# Sheet6.net
KiCad netlist of a schematic drawn in Altium Designer
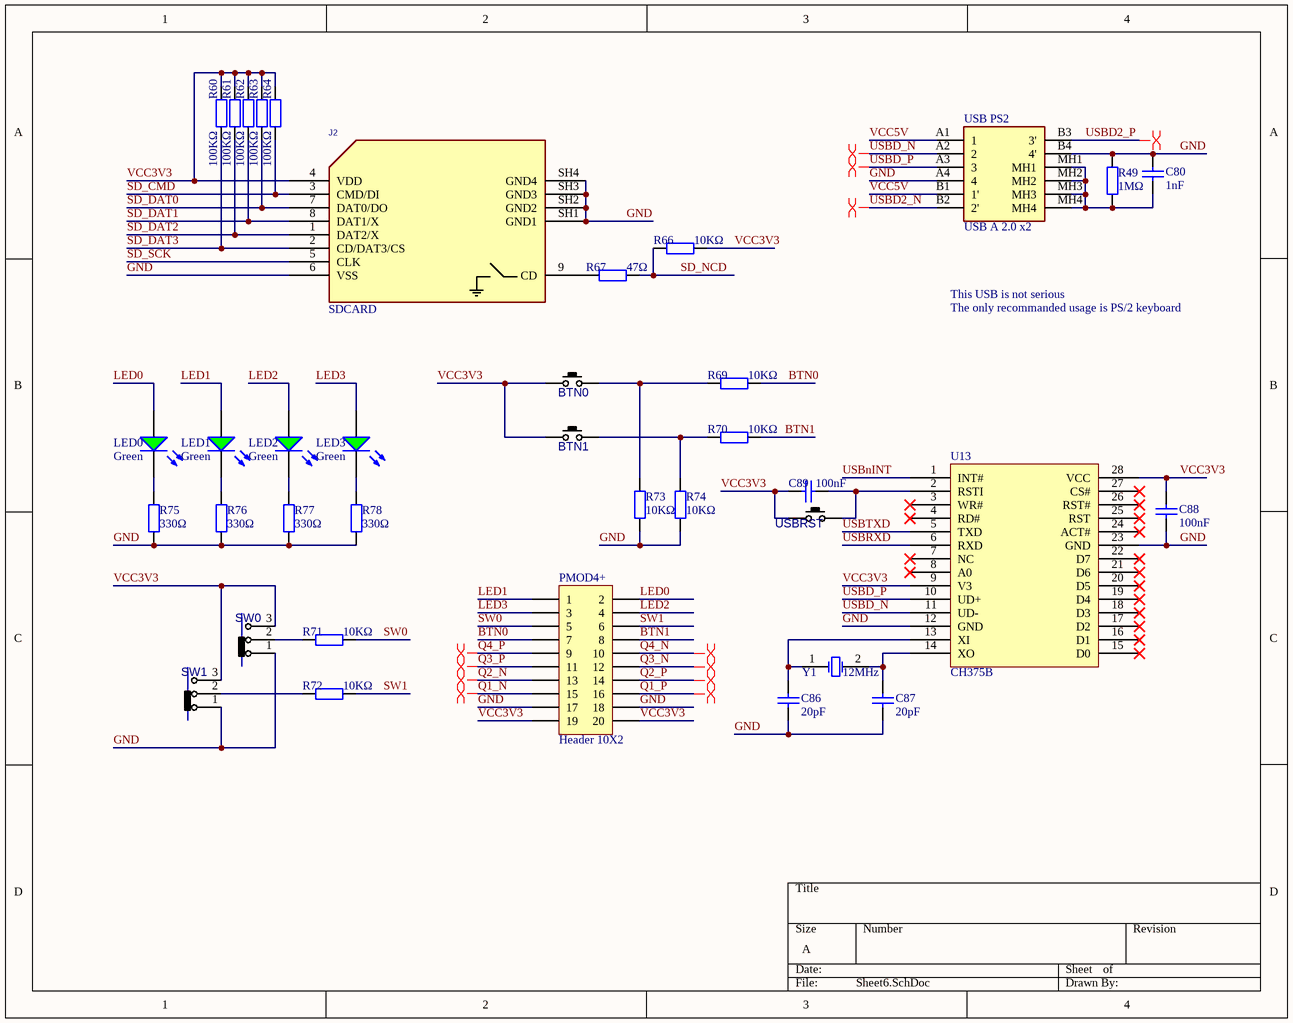
[diagram p0: Sheet6.SchDoc]

(export (version "E")
  (design (tool "Eeschema 10.0.6"))
  (components
    (comp (ref "BTN0")
      (value "PUSHBUTTON")
      (footprint "SWPBS_SPST_6X3X5")
      (description "SWITCH, PUSH BUTTON, TACTILE, SMD, SPST, 6X3.5X4.3mm")
      (fields (field (name "MANF") "Panasonic") (field (name "MANF_P#") "EVQ-PNF04M"))
      (libsource (lib "Switch Push Botton") (part "SWPBS_SPST_6X3X4"))
    )
    (comp (ref "BTN1")
      (value "PUSHBUTTON")
      (footprint "SWPBS_SPST_6X3X5")
      (description "SWITCH, PUSH BUTTON, TACTILE, SMD, SPST, 6X3.5X4.3mm")
      (fields (field (name "MANF") "Panasonic") (field (name "MANF_P#") "EVQ-PNF04M"))
      (libsource (lib "Switch Push Botton") (part "SWPBS_SPST_6X3X4"))
    )
    (comp (ref "C80")
      (value "1nF")
      (footprint "0805_C")
      (description "贴片电容")
      (libsource (lib "Cap") (part "0805 1nF (102) 10% 50V"))
    )
    (comp (ref "C86")
      (value "20pF")
      (footprint "0805_C")
      (description "贴片电容")
      (libsource (lib "Cap") (part "0805 20pF (200) 5% 50V"))
    )
    (comp (ref "C87")
      (value "20pF")
      (footprint "0805_C")
      (description "贴片电容")
      (libsource (lib "Cap") (part "0805 20pF (200) 5% 50V"))
    )
    (comp (ref "C88")
      (value "100nF")
      (footprint "1206_C")
      (description "贴片电容")
      (libsource (lib "Cap") (part "1206 100nF (104) 10% 50V"))
    )
    (comp (ref "C89")
      (value "100nF")
      (footprint "1206_C")
      (description "贴片电容")
      (libsource (lib "Cap") (part "1206 100nF (104) 10% 50V"))
    )
    (comp (ref "J2")
      (value "SDCARD")
      (footprint "SDMICRO_AT")
      (description "SD MICRO exist in Iran, Attend 112J-TDAR-R01")
      (fields (field (name "MANF") "Attend") (field (name "MANF_P#") "112J-TDAR-R01"))
      (libsource (lib "Connector Micro SD") (part "SOCKET_SDMICRO_AT"))
    )
    (comp (ref "LED0")
      (value "Green")
      (footprint "0805_LED_S1")
      (description "发光二极管")
      (libsource (lib "LED") (part "0805 翠绿"))
    )
    (comp (ref "LED1")
      (value "Green")
      (footprint "0805_LED_S1")
      (description "发光二极管")
      (libsource (lib "LED") (part "0805 翠绿"))
    )
    (comp (ref "LED2")
      (value "Green")
      (footprint "0805_LED_S1")
      (description "发光二极管")
      (libsource (lib "LED") (part "0805 翠绿"))
    )
    (comp (ref "LED3")
      (value "Green")
      (footprint "0805_LED_S1")
      (description "发光二极管")
      (libsource (lib "LED") (part "0805 翠绿"))
    )
    (comp (ref "PMOD4+")
      (value "Header 10X2")
      (footprint "HDR2X10")
      (description "Header, 10-Pin, Dual row")
      (fields (field (name "PUBLISHER") "Altium Limited"))
      (libsource (lib "Miscellaneous Connectors") (part "Header 10X2"))
    )
    (comp (ref "R49")
      (value "1MΩ")
      (footprint "0805_R")
      (description "贴片电阻")
      (libsource (lib "RES") (part "0805 1MΩ (1004) 1%"))
    )
    (comp (ref "R60")
      (value "100KΩ")
      (footprint "1206_R")
      (description "贴片电阻")
      (libsource (lib "RES") (part "1206 100KΩ (1003) 1%"))
    )
    (comp (ref "R61")
      (value "100KΩ")
      (footprint "1206_R")
      (description "贴片电阻")
      (libsource (lib "RES") (part "1206 100KΩ (1003) 1%"))
    )
    (comp (ref "R62")
      (value "100KΩ")
      (footprint "1206_R")
      (description "贴片电阻")
      (libsource (lib "RES") (part "1206 100KΩ (1003) 1%"))
    )
    (comp (ref "R63")
      (value "100KΩ")
      (footprint "1206_R")
      (description "贴片电阻")
      (libsource (lib "RES") (part "1206 100KΩ (1003) 1%"))
    )
    (comp (ref "R64")
      (value "100KΩ")
      (footprint "1206_R")
      (description "贴片电阻")
      (libsource (lib "RES") (part "1206 100KΩ (1003) 1%"))
    )
    (comp (ref "R66")
      (value "10KΩ")
      (footprint "1206_R")
      (description "贴片电阻")
      (libsource (lib "") (part "1206 10KΩ (1002) 1%_1"))
    )
    (comp (ref "R67")
      (value "47Ω")
      (footprint "0805_R")
      (description "贴片电阻")
      (libsource (lib "RES") (part "0805 47Ω (47R0) 1%"))
    )
    (comp (ref "R69")
      (value "10KΩ")
      (footprint "1206_R")
      (description "贴片电阻")
      (libsource (lib "") (part "1206 10KΩ (1002) 1%_1"))
    )
    (comp (ref "R70")
      (value "10KΩ")
      (footprint "1206_R")
      (description "贴片电阻")
      (libsource (lib "") (part "1206 10KΩ (1002) 1%_1"))
    )
    (comp (ref "R71")
      (value "10KΩ")
      (footprint "1206_R")
      (description "贴片电阻")
      (libsource (lib "") (part "1206 10KΩ (1002) 1%_1"))
    )
    (comp (ref "R72")
      (value "10KΩ")
      (footprint "1206_R")
      (description "贴片电阻")
      (libsource (lib "") (part "1206 10KΩ (1002) 1%_1"))
    )
    (comp (ref "R73")
      (value "10KΩ")
      (footprint "1206_R")
      (description "贴片电阻")
      (libsource (lib "RES") (part "1206 10KΩ (1002) 1%"))
    )
    (comp (ref "R74")
      (value "10KΩ")
      (footprint "1206_R")
      (description "贴片电阻")
      (libsource (lib "RES") (part "1206 10KΩ (1002) 1%"))
    )
    (comp (ref "R75")
      (value "330Ω")
      (footprint "0805_R")
      (description "贴片电阻")
      (libsource (lib "RES") (part "0805 330Ω (3300) 1%"))
    )
    (comp (ref "R76")
      (value "330Ω")
      (footprint "0805_R")
      (description "贴片电阻")
      (libsource (lib "RES") (part "0805 330Ω (3300) 1%"))
    )
    (comp (ref "R77")
      (value "330Ω")
      (footprint "0805_R")
      (description "贴片电阻")
      (libsource (lib "RES") (part "0805 330Ω (3300) 1%"))
    )
    (comp (ref "R78")
      (value "330Ω")
      (footprint "0805_R")
      (description "贴片电阻")
      (libsource (lib "RES") (part "0805 330Ω (3300) 1%"))
    )
    (comp (ref "SW0")
      (value "SlideSwitch")
      (footprint "SWSLIDT_SPDT_S_8X4")
      (description "SWITCH, SLIDE, SPDT, 8.6X4.3mm, THD")
      (fields (field (name "MANF") "C&K") (field (name "MANF_PART#") "OS102011MS2QN1"))
      (libsource (lib "Switch Slide") (part "SWSLIDT_SPDT_S_8X4"))
    )
    (comp (ref "SW1")
      (value "SlideSwitch")
      (footprint "SWSLIDT_SPDT_S_8X4")
      (description "SWITCH, SLIDE, SPDT, 8.6X4.3mm, THD")
      (fields (field (name "MANF") "C&K") (field (name "MANF_PART#") "OS102011MS2QN1"))
      (libsource (lib "Switch Slide") (part "SWSLIDT_SPDT_S_8X4"))
    )
    (comp (ref "U13")
      (value "CH375B")
      (footprint "SOIC-28_300mil")
      (description "USB")
      (libsource (lib "IC") (part "CH376S_[C14166]"))
    )
    (comp (ref "USB PS2")
      (value "USB A 2.0 x2")
      (footprint "SamacSys:0672983090")
      (description "Connector")
      (fields (field (name "MANUFACTURER_PART_NUMBER") "0672983090"))
      (libsource (lib "*") (part "0672983090"))
    )
    (comp (ref "USBRST")
      (value "PUSHBUTTON")
      (footprint "SWPBS_SPST_6X3X5")
      (description "SWITCH, PUSH BUTTON, TACTILE, SMD, SPST, 6X3.5X4.3mm")
      (fields (field (name "MANF") "Panasonic") (field (name "MANF_P#") "EVQ-PNF04M"))
      (libsource (lib "Switch Push Botton") (part "SWPBS_SPST_6X3X4"))
    )
    (comp (ref "Y1")
      (value "12MHz")
      (footprint "SMD-5032_2P")
      (description "贴片晶振")
      (libsource (lib "CrystalOscillator") (part "SMD-5032_2P 11.0592MHZ 20PF 20PPM"))
    )
  )
  (nets
    (net (code "1") (name "/BTN0") (class "Default")
      (node (ref "PMOD4+") (pin "7") (pinfunction "7_7") (pintype "passive"))
      (node (ref "R69") (pin "2") (pinfunction "2_2") (pintype "passive"))
    )
    (net (code "2") (name "/BTN1") (class "Default")
      (node (ref "PMOD4+") (pin "8") (pinfunction "8_8") (pintype "passive"))
      (node (ref "R70") (pin "2") (pinfunction "2_2") (pintype "passive"))
    )
    (net (code "3") (name "/GND") (class "Default")
      (node (ref "C80") (pin "1") (pinfunction "1_1") (pintype "passive"))
      (node (ref "C86") (pin "1") (pinfunction "1_1") (pintype "passive"))
      (node (ref "C87") (pin "1") (pinfunction "1_1") (pintype "passive"))
      (node (ref "C88") (pin "1") (pinfunction "1_1") (pintype "passive"))
      (node (ref "J2") (pin "6") (pinfunction "VSS_6") (pintype "passive"))
      (node (ref "J2") (pin "SH1") (pinfunction "GND1_SH1") (pintype "passive"))
      (node (ref "J2") (pin "SH2") (pinfunction "GND2_SH2") (pintype "passive"))
      (node (ref "J2") (pin "SH3") (pinfunction "GND3_SH3") (pintype "passive"))
      (node (ref "J2") (pin "SH4") (pinfunction "GND4_SH4") (pintype "passive"))
      (node (ref "PMOD4+") (pin "17") (pinfunction "17_17") (pintype "passive"))
      (node (ref "PMOD4+") (pin "18") (pinfunction "18_18") (pintype "passive"))
      (node (ref "R49") (pin "1") (pinfunction "1_1") (pintype "passive"))
      (node (ref "R73") (pin "1") (pinfunction "1_1") (pintype "passive"))
      (node (ref "R74") (pin "1") (pinfunction "1_1") (pintype "passive"))
      (node (ref "R75") (pin "1") (pinfunction "1_1") (pintype "passive"))
      (node (ref "R76") (pin "1") (pinfunction "1_1") (pintype "passive"))
      (node (ref "R77") (pin "1") (pinfunction "1_1") (pintype "passive"))
      (node (ref "R78") (pin "1") (pinfunction "1_1") (pintype "passive"))
      (node (ref "SW0") (pin "1") (pinfunction "P1_1") (pintype "passive"))
      (node (ref "SW1") (pin "1") (pinfunction "P1_1") (pintype "passive"))
      (node (ref "U13") (pin "12") (pinfunction "GND_12") (pintype "passive"))
      (node (ref "U13") (pin "23") (pinfunction "GND_23") (pintype "passive"))
      (node (ref "USB PS2") (pin "A4") (pinfunction "4_A4") (pintype "passive"))
      (node (ref "USB PS2") (pin "B4") (pinfunction "4'_B4") (pintype "passive"))
    )
    (net (code "4") (name "/LED0") (class "Default")
      (node (ref "LED0") (pin "A") (pinfunction "A_A") (pintype "passive"))
      (node (ref "PMOD4+") (pin "2") (pinfunction "2_2") (pintype "passive"))
    )
    (net (code "5") (name "/LED1") (class "Default")
      (node (ref "LED1") (pin "A") (pinfunction "A_A") (pintype "passive"))
      (node (ref "PMOD4+") (pin "1") (pinfunction "1_1") (pintype "passive"))
    )
    (net (code "6") (name "/LED2") (class "Default")
      (node (ref "LED2") (pin "A") (pinfunction "A_A") (pintype "passive"))
      (node (ref "PMOD4+") (pin "4") (pinfunction "4_4") (pintype "passive"))
    )
    (net (code "7") (name "/LED3") (class "Default")
      (node (ref "LED3") (pin "A") (pinfunction "A_A") (pintype "passive"))
      (node (ref "PMOD4+") (pin "3") (pinfunction "3_3") (pintype "passive"))
    )
    (net (code "8") (name "/Q1_N") (class "Default")
      (node (ref "PMOD4+") (pin "15") (pinfunction "15_15") (pintype "passive"))
    )
    (net (code "9") (name "/Q1_P") (class "Default")
      (node (ref "PMOD4+") (pin "16") (pinfunction "16_16") (pintype "passive"))
    )
    (net (code "10") (name "/Q2_N") (class "Default")
      (node (ref "PMOD4+") (pin "13") (pinfunction "13_13") (pintype "passive"))
    )
    (net (code "11") (name "/Q2_P") (class "Default")
      (node (ref "PMOD4+") (pin "14") (pinfunction "14_14") (pintype "passive"))
    )
    (net (code "12") (name "/Q3_N") (class "Default")
      (node (ref "PMOD4+") (pin "12") (pinfunction "12_12") (pintype "passive"))
    )
    (net (code "13") (name "/Q3_P") (class "Default")
      (node (ref "PMOD4+") (pin "11") (pinfunction "11_11") (pintype "passive"))
    )
    (net (code "14") (name "/Q4_N") (class "Default")
      (node (ref "PMOD4+") (pin "10") (pinfunction "10_10") (pintype "passive"))
    )
    (net (code "15") (name "/Q4_P") (class "Default")
      (node (ref "PMOD4+") (pin "9") (pinfunction "9_9") (pintype "passive"))
    )
    (net (code "16") (name "/SD_CMD") (class "Default")
      (node (ref "J2") (pin "3") (pinfunction "CMD/DI_3") (pintype "passive"))
      (node (ref "R64") (pin "1") (pinfunction "1_1") (pintype "passive"))
    )
    (net (code "17") (name "/SD_DAT0") (class "Default")
      (node (ref "J2") (pin "7") (pinfunction "DAT0/DO_7") (pintype "passive"))
      (node (ref "R63") (pin "1") (pinfunction "1_1") (pintype "passive"))
    )
    (net (code "18") (name "/SD_DAT1") (class "Default")
      (node (ref "J2") (pin "8") (pinfunction "DAT1/X_8") (pintype "passive"))
      (node (ref "R62") (pin "1") (pinfunction "1_1") (pintype "passive"))
    )
    (net (code "19") (name "/SD_DAT2") (class "Default")
      (node (ref "J2") (pin "1") (pinfunction "DAT2/X_1") (pintype "passive"))
      (node (ref "R61") (pin "1") (pinfunction "1_1") (pintype "passive"))
    )
    (net (code "20") (name "/SD_DAT3") (class "Default")
      (node (ref "J2") (pin "2") (pinfunction "CD/DAT3/CS_2") (pintype "passive"))
      (node (ref "R60") (pin "1") (pinfunction "1_1") (pintype "passive"))
    )
    (net (code "21") (name "/SD_NCD") (class "Default")
      (node (ref "R66") (pin "1") (pinfunction "1_1") (pintype "passive"))
      (node (ref "R67") (pin "2") (pinfunction "2_2") (pintype "passive"))
    )
    (net (code "22") (name "/SD_SCK") (class "Default")
      (node (ref "J2") (pin "5") (pinfunction "CLK_5") (pintype "passive"))
    )
    (net (code "23") (name "/SW0") (class "Default")
      (node (ref "PMOD4+") (pin "5") (pinfunction "5_5") (pintype "passive"))
      (node (ref "R71") (pin "2") (pinfunction "2_2") (pintype "passive"))
    )
    (net (code "24") (name "/SW1") (class "Default")
      (node (ref "PMOD4+") (pin "6") (pinfunction "6_6") (pintype "passive"))
      (node (ref "R72") (pin "2") (pinfunction "2_2") (pintype "passive"))
    )
    (net (code "25") (name "/USBD2_N") (class "Default")
      (node (ref "USB PS2") (pin "B2") (pinfunction "2'_B2") (pintype "passive"))
    )
    (net (code "26") (name "/USBD2_P") (class "Default")
      (node (ref "USB PS2") (pin "B3") (pinfunction "3'_B3") (pintype "passive"))
    )
    (net (code "27") (name "/USBD_N") (class "Default")
      (node (ref "U13") (pin "11") (pinfunction "UD-_11") (pintype "passive"))
      (node (ref "USB PS2") (pin "A2") (pinfunction "2_A2") (pintype "passive"))
    )
    (net (code "28") (name "/USBD_P") (class "Default")
      (node (ref "U13") (pin "10") (pinfunction "UD+_10") (pintype "passive"))
      (node (ref "USB PS2") (pin "A3") (pinfunction "3_A3") (pintype "passive"))
    )
    (net (code "29") (name "/USBRXD") (class "Default")
      (node (ref "U13") (pin "6") (pinfunction "RXD_6") (pintype "passive"))
    )
    (net (code "30") (name "/USBTXD") (class "Default")
      (node (ref "U13") (pin "5") (pinfunction "TXD_5") (pintype "passive"))
    )
    (net (code "31") (name "/USBnINT") (class "Default")
      (node (ref "U13") (pin "1") (pinfunction "INT#_1") (pintype "passive"))
    )
    (net (code "32") (name "/VCC3V3") (class "Default")
      (node (ref "BTN0") (pin "1") (pinfunction "P1_1") (pintype "passive"))
      (node (ref "BTN1") (pin "1") (pinfunction "P1_1") (pintype "passive"))
      (node (ref "C88") (pin "2") (pinfunction "2_2") (pintype "passive"))
      (node (ref "C89") (pin "2") (pinfunction "2_2") (pintype "passive"))
      (node (ref "J2") (pin "4") (pinfunction "VDD_4") (pintype "passive"))
      (node (ref "PMOD4+") (pin "19") (pinfunction "19_19") (pintype "passive"))
      (node (ref "PMOD4+") (pin "20") (pinfunction "20_20") (pintype "passive"))
      (node (ref "R60") (pin "2") (pinfunction "2_2") (pintype "passive"))
      (node (ref "R61") (pin "2") (pinfunction "2_2") (pintype "passive"))
      (node (ref "R62") (pin "2") (pinfunction "2_2") (pintype "passive"))
      (node (ref "R63") (pin "2") (pinfunction "2_2") (pintype "passive"))
      (node (ref "R64") (pin "2") (pinfunction "2_2") (pintype "passive"))
      (node (ref "R66") (pin "2") (pinfunction "2_2") (pintype "passive"))
      (node (ref "SW0") (pin "3") (pinfunction "P4_3") (pintype "passive"))
      (node (ref "SW1") (pin "3") (pinfunction "P4_3") (pintype "passive"))
      (node (ref "U13") (pin "28") (pinfunction "VCC_28") (pintype "passive"))
      (node (ref "U13") (pin "9") (pinfunction "V3_9") (pintype "passive"))
      (node (ref "USBRST") (pin "1") (pinfunction "P1_1") (pintype "passive"))
    )
    (net (code "33") (name "/VCC5V") (class "Default")
      (node (ref "USB PS2") (pin "A1") (pinfunction "1_A1") (pintype "passive"))
      (node (ref "USB PS2") (pin "B1") (pinfunction "1'_B1") (pintype "passive"))
    )
    (net (code "34") (name "Net-(BTN0-P3)") (class "Default")
      (node (ref "BTN0") (pin "2") (pinfunction "P3_2") (pintype "passive"))
      (node (ref "R69") (pin "1") (pinfunction "1_1") (pintype "passive"))
      (node (ref "R73") (pin "2") (pinfunction "2_2") (pintype "passive"))
    )
    (net (code "35") (name "Net-(BTN1-P3)") (class "Default")
      (node (ref "BTN1") (pin "2") (pinfunction "P3_2") (pintype "passive"))
      (node (ref "R70") (pin "1") (pinfunction "1_1") (pintype "passive"))
      (node (ref "R74") (pin "2") (pinfunction "2_2") (pintype "passive"))
    )
    (net (code "36") (name "Net-(C80-Pad2)") (class "Default")
      (node (ref "C80") (pin "2") (pinfunction "2_2") (pintype "passive"))
      (node (ref "R49") (pin "2") (pinfunction "2_2") (pintype "passive"))
      (node (ref "USB PS2") (pin "MH1") (pinfunction "MH1_MH1") (pintype "passive"))
      (node (ref "USB PS2") (pin "MH2") (pinfunction "MH2_MH2") (pintype "passive"))
      (node (ref "USB PS2") (pin "MH3") (pinfunction "MH3_MH3") (pintype "passive"))
      (node (ref "USB PS2") (pin "MH4") (pinfunction "MH4_MH4") (pintype "passive"))
    )
    (net (code "37") (name "Net-(J2-CD)") (class "Default")
      (node (ref "J2") (pin "9") (pinfunction "CD_9") (pintype "passive"))
      (node (ref "R67") (pin "1") (pinfunction "1_1") (pintype "passive"))
    )
    (net (code "38") (name "Net-(LED0-PadK)") (class "Default")
      (node (ref "LED0") (pin "K") (pinfunction "K_K") (pintype "passive"))
      (node (ref "R75") (pin "2") (pinfunction "2_2") (pintype "passive"))
    )
    (net (code "39") (name "Net-(LED1-PadK)") (class "Default")
      (node (ref "LED1") (pin "K") (pinfunction "K_K") (pintype "passive"))
      (node (ref "R76") (pin "2") (pinfunction "2_2") (pintype "passive"))
    )
    (net (code "40") (name "Net-(LED2-PadK)") (class "Default")
      (node (ref "LED2") (pin "K") (pinfunction "K_K") (pintype "passive"))
      (node (ref "R77") (pin "2") (pinfunction "2_2") (pintype "passive"))
    )
    (net (code "41") (name "Net-(LED3-PadK)") (class "Default")
      (node (ref "LED3") (pin "K") (pinfunction "K_K") (pintype "passive"))
      (node (ref "R78") (pin "2") (pinfunction "2_2") (pintype "passive"))
    )
    (net (code "42") (name "Net-(SW0-P3)") (class "Default")
      (node (ref "R71") (pin "1") (pinfunction "1_1") (pintype "passive"))
      (node (ref "SW0") (pin "2") (pinfunction "P3_2") (pintype "passive"))
    )
    (net (code "43") (name "Net-(SW1-P3)") (class "Default")
      (node (ref "R72") (pin "1") (pinfunction "1_1") (pintype "passive"))
      (node (ref "SW1") (pin "2") (pinfunction "P3_2") (pintype "passive"))
    )
    (net (code "44") (name "Net-(U13-RSTI)") (class "Default")
      (node (ref "C89") (pin "1") (pinfunction "1_1") (pintype "passive"))
      (node (ref "U13") (pin "2") (pinfunction "RSTI_2") (pintype "passive"))
      (node (ref "USBRST") (pin "2") (pinfunction "P3_2") (pintype "passive"))
    )
    (net (code "45") (name "Net-(U13-XI)") (class "Default")
      (node (ref "C86") (pin "2") (pinfunction "2_2") (pintype "passive"))
      (node (ref "U13") (pin "13") (pinfunction "XI_13") (pintype "passive"))
      (node (ref "Y1") (pin "1") (pinfunction "OSC1_1") (pintype "passive"))
    )
    (net (code "46") (name "Net-(U13-XO)") (class "Default")
      (node (ref "C87") (pin "2") (pinfunction "2_2") (pintype "passive"))
      (node (ref "U13") (pin "14") (pinfunction "XO_14") (pintype "passive"))
      (node (ref "Y1") (pin "2") (pinfunction "OSC2_2") (pintype "passive"))
    )
    (net (code "47") (name "unconnected-(U13-A0-Pad8)") (class "Default")
      (node (ref "U13") (pin "8") (pinfunction "A0_8") (pintype "passive+no_connect"))
    )
    (net (code "48") (name "unconnected-(U13-ACT#-Pad24)") (class "Default")
      (node (ref "U13") (pin "24") (pinfunction "ACT#_24") (pintype "passive+no_connect"))
    )
    (net (code "49") (name "unconnected-(U13-CS#-Pad27)") (class "Default")
      (node (ref "U13") (pin "27") (pinfunction "CS#_27") (pintype "passive+no_connect"))
    )
    (net (code "50") (name "unconnected-(U13-D0-Pad15)") (class "Default")
      (node (ref "U13") (pin "15") (pinfunction "D0_15") (pintype "passive+no_connect"))
    )
    (net (code "51") (name "unconnected-(U13-D1-Pad16)") (class "Default")
      (node (ref "U13") (pin "16") (pinfunction "D1_16") (pintype "passive+no_connect"))
    )
    (net (code "52") (name "unconnected-(U13-D2-Pad17)") (class "Default")
      (node (ref "U13") (pin "17") (pinfunction "D2_17") (pintype "passive+no_connect"))
    )
    (net (code "53") (name "unconnected-(U13-D3-Pad18)") (class "Default")
      (node (ref "U13") (pin "18") (pinfunction "D3_18") (pintype "passive+no_connect"))
    )
    (net (code "54") (name "unconnected-(U13-D4-Pad19)") (class "Default")
      (node (ref "U13") (pin "19") (pinfunction "D4_19") (pintype "passive+no_connect"))
    )
    (net (code "55") (name "unconnected-(U13-D5-Pad20)") (class "Default")
      (node (ref "U13") (pin "20") (pinfunction "D5_20") (pintype "passive+no_connect"))
    )
    (net (code "56") (name "unconnected-(U13-D6-Pad21)") (class "Default")
      (node (ref "U13") (pin "21") (pinfunction "D6_21") (pintype "passive+no_connect"))
    )
    (net (code "57") (name "unconnected-(U13-D7-Pad22)") (class "Default")
      (node (ref "U13") (pin "22") (pinfunction "D7_22") (pintype "passive+no_connect"))
    )
    (net (code "58") (name "unconnected-(U13-NC-Pad7)") (class "Default")
      (node (ref "U13") (pin "7") (pinfunction "NC_7") (pintype "passive+no_connect"))
    )
    (net (code "59") (name "unconnected-(U13-RD#-Pad4)") (class "Default")
      (node (ref "U13") (pin "4") (pinfunction "RD#_4") (pintype "passive+no_connect"))
    )
    (net (code "60") (name "unconnected-(U13-RST#-Pad26)") (class "Default")
      (node (ref "U13") (pin "26") (pinfunction "RST#_26") (pintype "passive+no_connect"))
    )
    (net (code "61") (name "unconnected-(U13-RST-Pad25)") (class "Default")
      (node (ref "U13") (pin "25") (pinfunction "RST_25") (pintype "passive+no_connect"))
    )
    (net (code "62") (name "unconnected-(U13-WR#-Pad3)") (class "Default")
      (node (ref "U13") (pin "3") (pinfunction "WR#_3") (pintype "passive+no_connect"))
    )
  )
)
